# BUCKCONVERTER_-_POWER.net
KiCad netlist of a schematic drawn in Altium Designer
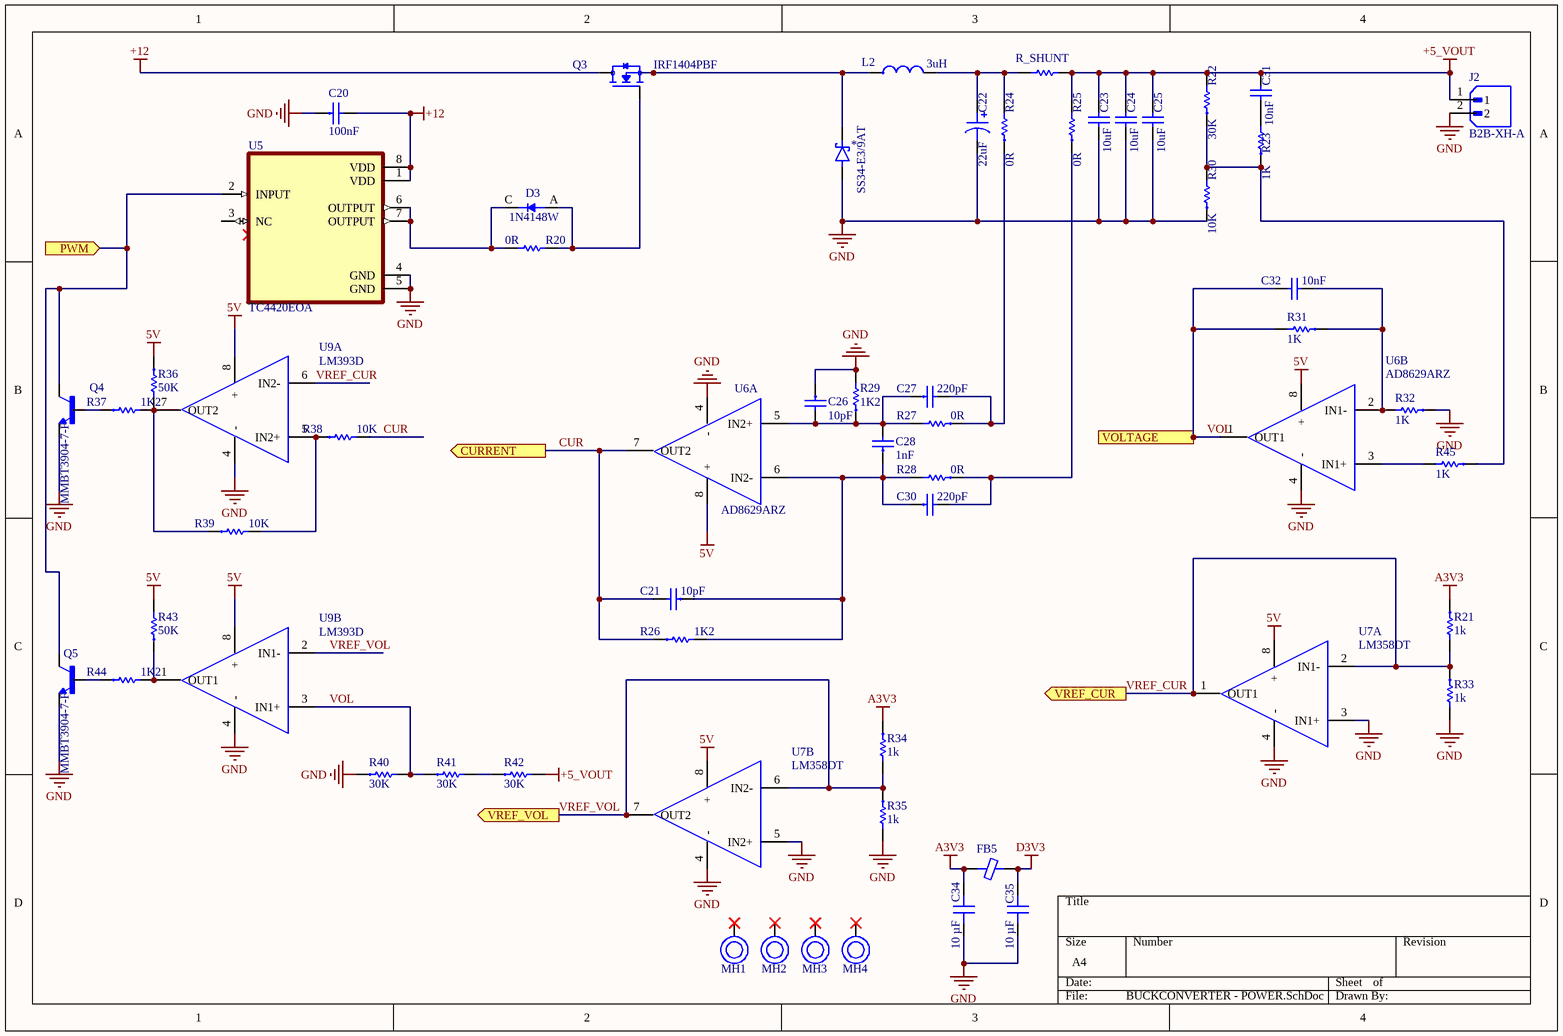
[diagram p0: BUCKCONVERTER - POWER.SchDoc]

(export (version "E")
  (design (tool "Eeschema 10.0.6"))
  (components
    (comp (ref "*")
      (value "SS34-E3/9AT")
      (footprint "SS34")
      (description "Rectifier Diode, Schottky, 1 Phase, 1 Element, 3A, 40V V(RRM), Silicon, DO-214AB")
      (fields (field (name "MANUFACTURER") "Vishay"))
      (libsource (lib "Schlib2") (part "SS34-E3/9AT"))
    )
    (comp (ref "C20")
      (value "100nF")
      (footprint "CAP-CER0402-20mil")
      (description "CAP CER 10uF 20% 6.3V X5R 0402 SMD")
      (libsource (lib "2502-GMQLITE-MAIN") (part "CAPCER0040 10uF 20% 6.3V X5R 0402 SMD"))
    )
    (comp (ref "C21")
      (value "10pF")
      (footprint "CAP-CER0603-0.8H")
      (description "CAP CER 220pF 10% 50V X7R 0603 SMD")
      (libsource (lib "2502-GMQLITE-MAIN") (part "CAPCER0003 220pF 10% 50V X7R 0603 SMD"))
    )
    (comp (ref "C22")
      (value "22uF")
      (footprint "330UF-5mm")
      (libsource (lib "Stm32_Flyback_Driver_250814_1") (part "CAP 47uF 63V_1"))
    )
    (comp (ref "C23")
      (value "10uF")
      (footprint "Cap cer 0603")
      (description "SMD Multilayer Ceramic Capacitor, 10 ï¿½F, 25 V, 0603 [1608 Metric], ï¿½ 20%, X5R")
      (fields
        (field (name "MANUFACTURER") "Murata")
        (field (name "MANUFACTURER PART NUMBER") "GRT188R61E106ME13D")
      )
      (libsource (lib "POWER_PIN_CAMERA") (part "GRT188R61E106ME13D"))
    )
    (comp (ref "C24")
      (value "10uF")
      (footprint "Cap cer 0603")
      (description "SMD Multilayer Ceramic Capacitor, 10 ï¿½F, 25 V, 0603 [1608 Metric], ï¿½ 20%, X5R")
      (fields
        (field (name "MANUFACTURER") "Murata")
        (field (name "MANUFACTURER PART NUMBER") "GRT188R61E106ME13D")
      )
      (libsource (lib "POWER_PIN_CAMERA") (part "GRT188R61E106ME13D"))
    )
    (comp (ref "C25")
      (value "10uF")
      (footprint "Cap cer 0603")
      (description "SMD Multilayer Ceramic Capacitor, 10 ï¿½F, 25 V, 0603 [1608 Metric], ï¿½ 20%, X5R")
      (fields
        (field (name "MANUFACTURER") "Murata")
        (field (name "MANUFACTURER PART NUMBER") "GRT188R61E106ME13D")
      )
      (libsource (lib "POWER_PIN_CAMERA") (part "GRT188R61E106ME13D"))
    )
    (comp (ref "C26")
      (value "10pF")
      (footprint "CAP-CER0603-0.8H")
      (description "CAP CER 220pF 10% 50V X7R 0603 SMD")
      (libsource (lib "2502-GMQLITE-MAIN") (part "CAPCER0003 220pF 10% 50V X7R 0603 SMD"))
    )
    (comp (ref "C27")
      (value "220pF")
      (footprint "CAP-CER0603-0.8H")
      (description "CAP CER 220pF 10% 50V X7R 0603 SMD")
      (libsource (lib "2502-GMQLITE-MAIN") (part "CAPCER0003 220pF 10% 50V X7R 0603 SMD"))
    )
    (comp (ref "C28")
      (value "1nF")
      (footprint "CAP-CER0603-0.8H")
      (description "CAP CER 220pF 10% 50V X7R 0603 SMD")
      (libsource (lib "2502-GMQLITE-MAIN") (part "CAPCER0003 220pF 10% 50V X7R 0603 SMD"))
    )
    (comp (ref "C30")
      (value "220pF")
      (footprint "CAP-CER0603-0.8H")
      (description "CAP CER 220pF 10% 50V X7R 0603 SMD")
      (libsource (lib "2502-GMQLITE-MAIN") (part "CAPCER0003 220pF 10% 50V X7R 0603 SMD"))
    )
    (comp (ref "C31")
      (value "10nF")
      (footprint "Cap cer 0603")
      (description "SMD Multilayer Ceramic Capacitor, 10 ï¿½F, 25 V, 0603 [1608 Metric], ï¿½ 20%, X5R")
      (fields
        (field (name "MANUFACTURER") "Murata")
        (field (name "MANUFACTURER PART NUMBER") "GRT188R61E106ME13D")
      )
      (libsource (lib "POWER_PIN_CAMERA") (part "GRT188R61E106ME13D"))
    )
    (comp (ref "C32")
      (value "10nF")
      (footprint "Cap cer 0603")
      (description "SMD Multilayer Ceramic Capacitor, 10 ï¿½F, 25 V, 0603 [1608 Metric], ï¿½ 20%, X5R")
      (fields
        (field (name "MANUFACTURER") "Murata")
        (field (name "MANUFACTURER PART NUMBER") "GRT188R61E106ME13D")
      )
      (libsource (lib "POWER_PIN_CAMERA") (part "GRT188R61E106ME13D"))
    )
    (comp (ref "C34")
      (value "10 µF")
      (footprint "CAP 0603")
      (description "CAP0603 X7R 10UF 10% 10V")
      (fields
        (field (name "PART NUMBER") "GMC10X7R106K10NT")
        (field (name "MANUFACTURER") "Cal-Chip Electronics, Inc.")
      )
      (libsource (lib "Celestial Altium Library - altium_library") (part "Capacitor"))
    )
    (comp (ref "C35")
      (value "10 µF")
      (footprint "CAP 0603")
      (description "CAP0603 X7R 10UF 10% 10V")
      (fields
        (field (name "PART NUMBER") "GMC10X7R106K10NT")
        (field (name "MANUFACTURER") "Cal-Chip Electronics, Inc.")
      )
      (libsource (lib "Celestial Altium Library - altium_library") (part "Capacitor"))
    )
    (comp (ref "D3")
      (value "1N4148W")
      (footprint "1N4148")
      (description "Small Signal Diode, Single, 100 V, 300 Ma, 1.25 V, 4 Ns, 2 A Rohs Compliant: Yes")
      (fields (field (name "MANUFACTURER") "Diodes") (field (name "MANUFACTURER PART NUMBER") "1N4148W-7-F"))
      (libsource (lib "POWER_PIN_CAMERA") (part "1N4148W-7-F"))
    )
    (comp (ref "FB5")
      (value "330 Ohms @ 100 MHz")
      (footprint "FB_0603")
      (description "FERRITE BEAD 330 OHM 0603 1LN")
      (fields
        (field (name "PART NUMBER") "BLM18KG331SH1D")
        (field (name "MANUFACTURER") "Murata Electronics")
      )
      (libsource (lib "Celestial Altium Library - altium_library") (part "Ferrite Chip"))
    )
    (comp (ref "J2")
      (value "B2B-XH-A")
      (footprint "JST_B2B-XH-A")
      (fields (field (name "MF") "{'manufacturer': u'JST Sales America Inc.'}"))
      (libsource (lib "B2B-XH-A") (part "B2B-XH-A"))
    )
    (comp (ref "L2")
      (value "3uH")
      (footprint "IND-06030-1uH")
      (description "IND MOI 1W2T 1.5uH 20% 14A 0630 SMD")
      (libsource (lib "2502-GMQLITE-MAIN") (part "INDMOI0013 1W2T 1.5uH 20% 14A 0630 SMD"))
    )
    (comp (ref "MH1") (value "MOUNTING HOLE") (footprint "M3") (libsource (lib "INVERTER") (part "MH")))
    (comp (ref "MH2") (value "MOUNTING HOLE") (footprint "M3") (libsource (lib "INVERTER") (part "MH")))
    (comp (ref "MH3") (value "MOUNTING HOLE") (footprint "M3") (libsource (lib "INVERTER") (part "MH")))
    (comp (ref "MH4") (value "MOUNTING HOLE") (footprint "M3") (libsource (lib "INVERTER") (part "MH")))
    (comp (ref "Q3")
      (value "IRF1404PBF")
      (footprint "TO220 AB")
      (description "Single N-Channel 40 V 0.004 Ohm 196 nC HEXFET® Power Mosfet - TO-220-3")
      (fields (field (name "MANUFACTURER") "Infineon"))
      (libsource (lib "Schlib2") (part "IRF1404PBF"))
    )
    (comp (ref "Q4")
      (value "MMBT3904-7-F")
      (footprint "MMBT3904")
      (description "Transistor General Purpose BJT NPN 40 Volt 0.2A Automotive 3-Pin SOT-23")
      (fields (field (name "MANUFACTURER") "Diodes Zetex"))
      (libsource (lib "POWER_PIN_CAMERA") (part "MMBT3904-7-F"))
    )
    (comp (ref "Q5")
      (value "MMBT3904-7-F")
      (footprint "MMBT3904")
      (description "Transistor General Purpose BJT NPN 40 Volt 0.2A Automotive 3-Pin SOT-23")
      (fields (field (name "MANUFACTURER") "Diodes Zetex"))
      (libsource (lib "POWER_PIN_CAMERA") (part "MMBT3904-7-F"))
    )
    (comp (ref "R20")
      (value "0R")
      (footprint "Res 0603")
      (description "Res Thick Film 0603 0 Ohm Pad SMD T/R")
      (fields
        (field (name "MANUFACTURER") "Vishay")
        (field (name "MANUFACTURER PART NUMBER") "CRCW06030000Z0EBC")
      )
      (libsource (lib "POWER_PIN_CAMERA") (part "Resistor 0R"))
    )
    (comp (ref "R21")
      (value "1k")
      (footprint "RES-CHP0402-0.35H")
      (description "RES CHP 33K 1% 1/16W 0402 SMD")
      (libsource (lib "2502-GMQLITE-MAIN") (part "RESCHP0085 33K 1% 0402 SMD"))
    )
    (comp (ref "R22")
      (value "30K")
      (footprint "RES-CHP0603-0.45H-272")
      (description "RES CHP 2K7 1% 1/10W 0603 SMD")
      (libsource (lib "2502-GMQLITE-MAIN") (part "RESCHP0195 2K7 1% 0603 SMD"))
    )
    (comp (ref "R23")
      (value "1K")
      (footprint "RES-CHP0603-0.45H-272")
      (description "RES CHP 2K7 1% 1/10W 0603 SMD")
      (libsource (lib "2502-GMQLITE-MAIN") (part "RESCHP0195 2K7 1% 0603 SMD"))
    )
    (comp (ref "R24")
      (value "0R")
      (footprint "RES-CHP0603-0.45H-272")
      (description "RES CHP 2K7 1% 1/10W 0603 SMD")
      (libsource (lib "2502-GMQLITE-MAIN") (part "RESCHP0195 2K7 1% 0603 SMD"))
    )
    (comp (ref "R25")
      (value "0R")
      (footprint "RES-CHP0603-0.45H-272")
      (description "RES CHP 2K7 1% 1/10W 0603 SMD")
      (libsource (lib "2502-GMQLITE-MAIN") (part "RESCHP0195 2K7 1% 0603 SMD"))
    )
    (comp (ref "R26")
      (value "1K2")
      (footprint "RES-CHP0603-0.45H-272")
      (description "RES CHP 2K7 1% 1/10W 0603 SMD")
      (libsource (lib "2502-GMQLITE-MAIN") (part "RESCHP0195 2K7 1% 0603 SMD"))
    )
    (comp (ref "R27")
      (value "0R")
      (footprint "RES-CHP0603-0.45H-272")
      (description "RES CHP 2K7 1% 1/10W 0603 SMD")
      (libsource (lib "2502-GMQLITE-MAIN") (part "RESCHP0195 2K7 1% 0603 SMD"))
    )
    (comp (ref "R28")
      (value "0R")
      (footprint "RES-CHP0603-0.45H-272")
      (description "RES CHP 2K7 1% 1/10W 0603 SMD")
      (libsource (lib "2502-GMQLITE-MAIN") (part "RESCHP0195 2K7 1% 0603 SMD"))
    )
    (comp (ref "R29")
      (value "1K2")
      (footprint "RES-CHP0603-0.45H-272")
      (description "RES CHP 2K7 1% 1/10W 0603 SMD")
      (libsource (lib "2502-GMQLITE-MAIN") (part "RESCHP0195 2K7 1% 0603 SMD"))
    )
    (comp (ref "R30")
      (value "10K")
      (footprint "RES-CHP0603-0.45H-272")
      (description "RES CHP 2K7 1% 1/10W 0603 SMD")
      (libsource (lib "2502-GMQLITE-MAIN") (part "RESCHP0195 2K7 1% 0603 SMD"))
    )
    (comp (ref "R31")
      (value "1K")
      (footprint "RES-CHP0603-0.45H-272")
      (description "RES CHP 2K7 1% 1/10W 0603 SMD")
      (libsource (lib "2502-GMQLITE-MAIN") (part "RESCHP0195 2K7 1% 0603 SMD"))
    )
    (comp (ref "R32")
      (value "1K")
      (footprint "RES-CHP0603-0.45H-272")
      (description "RES CHP 2K7 1% 1/10W 0603 SMD")
      (libsource (lib "2502-GMQLITE-MAIN") (part "RESCHP0195 2K7 1% 0603 SMD"))
    )
    (comp (ref "R33")
      (value "1k")
      (footprint "RES-CHP0402-0.35H")
      (description "RES CHP 33K 1% 1/16W 0402 SMD")
      (libsource (lib "2502-GMQLITE-MAIN") (part "RESCHP0085 33K 1% 0402 SMD"))
    )
    (comp (ref "R34")
      (value "1k")
      (footprint "RES-CHP0402-0.35H")
      (description "RES CHP 33K 1% 1/16W 0402 SMD")
      (libsource (lib "2502-GMQLITE-MAIN") (part "RESCHP0085 33K 1% 0402 SMD"))
    )
    (comp (ref "R35")
      (value "1k")
      (footprint "RES-CHP0402-0.35H")
      (description "RES CHP 33K 1% 1/16W 0402 SMD")
      (libsource (lib "2502-GMQLITE-MAIN") (part "RESCHP0085 33K 1% 0402 SMD"))
    )
    (comp (ref "R36")
      (value "50K")
      (footprint "RES-CHP0603-0.45H-272")
      (description "RES CHP 2K7 1% 1/10W 0603 SMD")
      (libsource (lib "2502-GMQLITE-MAIN") (part "RESCHP0195 2K7 1% 0603 SMD"))
    )
    (comp (ref "R37")
      (value "1K2")
      (footprint "RES-CHP0603-0.45H-272")
      (description "RES CHP 2K7 1% 1/10W 0603 SMD")
      (libsource (lib "2502-GMQLITE-MAIN") (part "RESCHP0195 2K7 1% 0603 SMD"))
    )
    (comp (ref "R38")
      (value "10K")
      (footprint "RES-CHP0603-0.45H-272")
      (description "RES CHP 2K7 1% 1/10W 0603 SMD")
      (libsource (lib "2502-GMQLITE-MAIN") (part "RESCHP0195 2K7 1% 0603 SMD"))
    )
    (comp (ref "R39")
      (value "10K")
      (footprint "RES-CHP0603-0.45H-272")
      (description "RES CHP 2K7 1% 1/10W 0603 SMD")
      (libsource (lib "2502-GMQLITE-MAIN") (part "RESCHP0195 2K7 1% 0603 SMD"))
    )
    (comp (ref "R40")
      (value "30K")
      (footprint "RES-CHP0402-0.35H")
      (description "RES CHP 33K 1% 1/16W 0402 SMD")
      (libsource (lib "2502-GMQLITE-MAIN") (part "RESCHP0085 33K 1% 0402 SMD"))
    )
    (comp (ref "R41")
      (value "30K")
      (footprint "RES-CHP0402-0.35H")
      (description "RES CHP 33K 1% 1/16W 0402 SMD")
      (libsource (lib "2502-GMQLITE-MAIN") (part "RESCHP0085 33K 1% 0402 SMD"))
    )
    (comp (ref "R42")
      (value "30K")
      (footprint "RES-CHP0402-0.35H")
      (description "RES CHP 33K 1% 1/16W 0402 SMD")
      (libsource (lib "2502-GMQLITE-MAIN") (part "RESCHP0085 33K 1% 0402 SMD"))
    )
    (comp (ref "R43")
      (value "50K")
      (footprint "RES-CHP0603-0.45H-272")
      (description "RES CHP 2K7 1% 1/10W 0603 SMD")
      (libsource (lib "2502-GMQLITE-MAIN") (part "RESCHP0195 2K7 1% 0603 SMD"))
    )
    (comp (ref "R44")
      (value "1K2")
      (footprint "RES-CHP0603-0.45H-272")
      (description "RES CHP 2K7 1% 1/10W 0603 SMD")
      (libsource (lib "2502-GMQLITE-MAIN") (part "RESCHP0195 2K7 1% 0603 SMD"))
    )
    (comp (ref "R45")
      (value "1K")
      (footprint "RES-CHP0603-0.45H-272")
      (description "RES CHP 2K7 1% 1/10W 0603 SMD")
      (libsource (lib "2502-GMQLITE-MAIN") (part "RESCHP0195 2K7 1% 0603 SMD"))
    )
    (comp (ref "R_SHUNT")
      (value "0.01R")
      (footprint "R_SHUNT")
      (libsource (lib "Stm32_Flyback_Driver_250814_1") (part "R_SHUNT"))
    )
    (comp (ref "U5")
      (value "TC4420EOA")
      (footprint "SOIC127P600X175-8N")
      (fields (field (name "MF") "Microchip"))
      (libsource (lib "TC4420EOA") (part "TC4420EOA"))
    )
    (comp (ref "U6")
      (value "AD8629ARZ")
      (footprint "AD8629ARZ")
      (description "IC OPAMP ZERO-DRIFT 2 CIRC 8SOIC Zero-Drift Amplifier 2 Circuit Rail-to-Rail 8-SOIC")
      (fields (field (name "MANUFACTURER") "Analog Devices"))
      (libsource (lib "Schlib2") (part "AD8629ARZ"))
    )
    (comp (ref "U7")
      (value "LM358DT")
      (footprint "SOIC 8")
      (description "Operational Amplifier, 2-Channels, 1.1 MHz, 0.6 V/us, 3 V to 30 V, 8 Pins, SOIC")
      (fields (field (name "MANUFACTURER") "STMicroelectronics"))
      (libsource (lib "Stm32_Flyback_Driver_250814_1") (part "LM358DT"))
    )
    (comp (ref "U9")
      (value "LM393D")
      (footprint "LM393")
      (description "LM393 Series Dual 36 V 250 nA SMT Low Power Voltage Comparator - SOIC-8")
      (fields (field (name "MANUFACTURER") "STMicroelectronics"))
      (libsource (lib "BUCKCONVERTER") (part "LM393D"))
    )
  )
  (nets
    (net (code "1") (name "+5_VOUT") (class "Default")
      (node (ref "C23") (pin "2") (pinfunction "2_2") (pintype "passive"))
      (node (ref "C24") (pin "2") (pinfunction "2_2") (pintype "passive"))
      (node (ref "C25") (pin "2") (pinfunction "2_2") (pintype "passive"))
      (node (ref "C31") (pin "2") (pinfunction "2_2") (pintype "passive"))
      (node (ref "J2") (pin "1") (pinfunction "1_1") (pintype "passive"))
      (node (ref "R22") (pin "2") (pinfunction "2_2") (pintype "passive"))
      (node (ref "R25") (pin "2") (pinfunction "2_2") (pintype "passive"))
      (node (ref "R42") (pin "2") (pinfunction "2_2") (pintype "passive"))
      (node (ref "R_SHUNT") (pin "2") (pinfunction "2_2") (pintype "passive"))
    )
    (net (code "2") (name "+12") (class "Default")
      (node (ref "C20") (pin "2") (pinfunction "2_2") (pintype "passive"))
      (node (ref "Q3") (pin "2") (pinfunction "D_2") (pintype "passive"))
      (node (ref "U5") (pin "1") (pinfunction "VDD_1") (pintype "power_in"))
      (node (ref "U5") (pin "8") (pinfunction "VDD_8") (pintype "power_in"))
    )
    (net (code "3") (name "/CUR") (class "Default")
      (node (ref "C21") (pin "2") (pinfunction "2_2") (pintype "passive"))
      (node (ref "R26") (pin "1") (pinfunction "1_1") (pintype "passive"))
      (node (ref "R38") (pin "2") (pinfunction "2_2") (pintype "passive"))
      (node (ref "U6") (pin "7") (pinfunction "OUT2_7") (pintype "passive"))
    )
    (net (code "4") (name "/PWM") (class "Default")
      (node (ref "Q4") (pin "C") (pinfunction "C_C") (pintype "passive"))
      (node (ref "Q5") (pin "C") (pinfunction "C_C") (pintype "passive"))
      (node (ref "U5") (pin "2") (pinfunction "INPUT_2") (pintype "input"))
    )
    (net (code "5") (name "/VOL") (class "Default")
      (node (ref "C32") (pin "2") (pinfunction "2_2") (pintype "passive"))
      (node (ref "R31") (pin "2") (pinfunction "2_2") (pintype "passive"))
      (node (ref "R40") (pin "2") (pinfunction "2_2") (pintype "passive"))
      (node (ref "R41") (pin "1") (pinfunction "1_1") (pintype "passive"))
      (node (ref "U6") (pin "1") (pinfunction "OUT1_1") (pintype "passive"))
      (node (ref "U9") (pin "3") (pinfunction "IN1+_3") (pintype "passive"))
    )
    (net (code "6") (name "/VREF_CUR") (class "Default")
      (node (ref "R21") (pin "2") (pinfunction "2_2") (pintype "passive"))
      (node (ref "R33") (pin "1") (pinfunction "1_1") (pintype "passive"))
      (node (ref "U7") (pin "1") (pinfunction "OUT1_1") (pintype "passive"))
      (node (ref "U7") (pin "2") (pinfunction "IN1-_2") (pintype "passive"))
      (node (ref "U9") (pin "6") (pinfunction "IN2-_6") (pintype "passive"))
    )
    (net (code "7") (name "/VREF_VOL") (class "Default")
      (node (ref "R34") (pin "2") (pinfunction "2_2") (pintype "passive"))
      (node (ref "R35") (pin "1") (pinfunction "1_1") (pintype "passive"))
      (node (ref "U7") (pin "6") (pinfunction "IN2-_6") (pintype "passive"))
      (node (ref "U7") (pin "7") (pinfunction "OUT2_7") (pintype "passive"))
      (node (ref "U9") (pin "2") (pinfunction "IN1-_2") (pintype "passive"))
    )
    (net (code "8") (name "5V") (class "Default")
      (node (ref "R36") (pin "1") (pinfunction "1_1") (pintype "passive"))
      (node (ref "R43") (pin "2") (pinfunction "2_2") (pintype "passive"))
      (node (ref "U6") (pin "8") (pinfunction "+_8") (pintype "passive"))
      (node (ref "U7") (pin "8") (pinfunction "+_8") (pintype "passive"))
      (node (ref "U9") (pin "8") (pinfunction "+_8") (pintype "passive"))
    )
    (net (code "9") (name "A3V3") (class "Default")
      (node (ref "C34") (pin "2") (pinfunction "2_2") (pintype "passive"))
      (node (ref "FB5") (pin "1") (pinfunction "1_1") (pintype "passive"))
      (node (ref "R21") (pin "1") (pinfunction "1_1") (pintype "passive"))
      (node (ref "R34") (pin "1") (pinfunction "1_1") (pintype "passive"))
    )
    (net (code "10") (name "D3V3") (class "Default")
      (node (ref "C35") (pin "2") (pinfunction "2_2") (pintype "passive"))
      (node (ref "FB5") (pin "2") (pinfunction "2_2") (pintype "passive"))
    )
    (net (code "11") (name "GND") (class "Default")
      (node (ref "*") (pin "A") (pinfunction "A_A") (pintype "passive"))
      (node (ref "C20") (pin "1") (pinfunction "1_1") (pintype "passive"))
      (node (ref "C22") (pin "2") (pinfunction "2_2") (pintype "passive"))
      (node (ref "C23") (pin "1") (pinfunction "1_1") (pintype "passive"))
      (node (ref "C24") (pin "1") (pinfunction "1_1") (pintype "passive"))
      (node (ref "C25") (pin "1") (pinfunction "1_1") (pintype "passive"))
      (node (ref "C26") (pin "1") (pinfunction "1_1") (pintype "passive"))
      (node (ref "C34") (pin "1") (pinfunction "1_1") (pintype "passive"))
      (node (ref "C35") (pin "1") (pinfunction "1_1") (pintype "passive"))
      (node (ref "J2") (pin "2") (pinfunction "2_2") (pintype "passive"))
      (node (ref "Q4") (pin "E") (pinfunction "E_E") (pintype "passive"))
      (node (ref "Q5") (pin "E") (pinfunction "E_E") (pintype "passive"))
      (node (ref "R29") (pin "2") (pinfunction "2_2") (pintype "passive"))
      (node (ref "R30") (pin "1") (pinfunction "1_1") (pintype "passive"))
      (node (ref "R32") (pin "1") (pinfunction "1_1") (pintype "passive"))
      (node (ref "R33") (pin "2") (pinfunction "2_2") (pintype "passive"))
      (node (ref "R35") (pin "2") (pinfunction "2_2") (pintype "passive"))
      (node (ref "R40") (pin "1") (pinfunction "1_1") (pintype "passive"))
      (node (ref "U5") (pin "4") (pinfunction "GND_4") (pintype "power_in"))
      (node (ref "U5") (pin "5") (pinfunction "GND_5") (pintype "power_in"))
      (node (ref "U6") (pin "4") (pinfunction "-_4") (pintype "passive"))
      (node (ref "U7") (pin "3") (pinfunction "IN1+_3") (pintype "passive"))
      (node (ref "U7") (pin "4") (pinfunction "-_4") (pintype "passive"))
      (node (ref "U7") (pin "5") (pinfunction "IN2+_5") (pintype "passive"))
      (node (ref "U9") (pin "4") (pinfunction "-_4") (pintype "passive"))
    )
    (net (code "12") (name "Net-(*-K)") (class "Default")
      (node (ref "*") (pin "C") (pinfunction "K_C") (pintype "passive"))
      (node (ref "L2") (pin "1") (pinfunction "1_1") (pintype "passive"))
      (node (ref "Q3") (pin "3") (pinfunction "S_3") (pintype "passive"))
    )
    (net (code "13") (name "Net-(C22-Pad1)") (class "Default")
      (node (ref "C22") (pin "1") (pinfunction "1_1") (pintype "passive"))
      (node (ref "L2") (pin "2") (pinfunction "2_2") (pintype "passive"))
      (node (ref "R24") (pin "2") (pinfunction "2_2") (pintype "passive"))
      (node (ref "R_SHUNT") (pin "1") (pinfunction "1_1") (pintype "passive"))
    )
    (net (code "14") (name "Net-(C27-Pad2)") (class "Default")
      (node (ref "C27") (pin "2") (pinfunction "2_2") (pintype "passive"))
      (node (ref "R24") (pin "1") (pinfunction "1_1") (pintype "passive"))
      (node (ref "R27") (pin "1") (pinfunction "1_1") (pintype "passive"))
    )
    (net (code "15") (name "Net-(C30-Pad2)") (class "Default")
      (node (ref "C30") (pin "2") (pinfunction "2_2") (pintype "passive"))
      (node (ref "R25") (pin "1") (pinfunction "1_1") (pintype "passive"))
      (node (ref "R28") (pin "1") (pinfunction "1_1") (pintype "passive"))
    )
    (net (code "16") (name "Net-(C31-Pad1)") (class "Default")
      (node (ref "C31") (pin "1") (pinfunction "1_1") (pintype "passive"))
      (node (ref "R23") (pin "2") (pinfunction "2_2") (pintype "passive"))
    )
    (net (code "17") (name "Net-(D3-K)") (class "Default")
      (node (ref "D3") (pin "C") (pinfunction "K_C") (pintype "passive"))
      (node (ref "R20") (pin "1") (pinfunction "1_1") (pintype "passive"))
      (node (ref "U5") (pin "6") (pinfunction "OUTPUT_6") (pintype "output"))
      (node (ref "U5") (pin "7") (pinfunction "OUTPUT_7") (pintype "output"))
    )
    (net (code "18") (name "Net-(Q3-G)") (class "Default")
      (node (ref "D3") (pin "A") (pinfunction "A_A") (pintype "passive"))
      (node (ref "Q3") (pin "1") (pinfunction "G_1") (pintype "passive"))
      (node (ref "R20") (pin "2") (pinfunction "2_2") (pintype "passive"))
    )
    (net (code "19") (name "Net-(Q4-PadB)") (class "Default")
      (node (ref "Q4") (pin "B") (pinfunction "B_B") (pintype "passive"))
      (node (ref "R37") (pin "1") (pinfunction "1_1") (pintype "passive"))
    )
    (net (code "20") (name "Net-(Q5-PadB)") (class "Default")
      (node (ref "Q5") (pin "B") (pinfunction "B_B") (pintype "passive"))
      (node (ref "R44") (pin "1") (pinfunction "1_1") (pintype "passive"))
    )
    (net (code "21") (name "Net-(R22-Pad1)") (class "Default")
      (node (ref "R22") (pin "1") (pinfunction "1_1") (pintype "passive"))
      (node (ref "R23") (pin "1") (pinfunction "1_1") (pintype "passive"))
      (node (ref "R30") (pin "2") (pinfunction "2_2") (pintype "passive"))
      (node (ref "R45") (pin "1") (pinfunction "1_1") (pintype "passive"))
    )
    (net (code "22") (name "Net-(R41-Pad2)") (class "Default")
      (node (ref "R41") (pin "2") (pinfunction "2_2") (pintype "passive"))
      (node (ref "R42") (pin "1") (pinfunction "1_1") (pintype "passive"))
    )
    (net (code "23") (name "Net-(U6A-IN2+)") (class "Default")
      (node (ref "C26") (pin "2") (pinfunction "2_2") (pintype "passive"))
      (node (ref "C27") (pin "1") (pinfunction "1_1") (pintype "passive"))
      (node (ref "C28") (pin "2") (pinfunction "2_2") (pintype "passive"))
      (node (ref "R27") (pin "2") (pinfunction "2_2") (pintype "passive"))
      (node (ref "R29") (pin "1") (pinfunction "1_1") (pintype "passive"))
      (node (ref "U6") (pin "5") (pinfunction "IN2+_5") (pintype "passive"))
    )
    (net (code "24") (name "Net-(U6A-IN2-)") (class "Default")
      (node (ref "C21") (pin "1") (pinfunction "1_1") (pintype "passive"))
      (node (ref "C28") (pin "1") (pinfunction "1_1") (pintype "passive"))
      (node (ref "C30") (pin "1") (pinfunction "1_1") (pintype "passive"))
      (node (ref "R26") (pin "2") (pinfunction "2_2") (pintype "passive"))
      (node (ref "R28") (pin "2") (pinfunction "2_2") (pintype "passive"))
      (node (ref "U6") (pin "6") (pinfunction "IN2-_6") (pintype "passive"))
    )
    (net (code "25") (name "Net-(U6B-IN1+)") (class "Default")
      (node (ref "R45") (pin "2") (pinfunction "2_2") (pintype "passive"))
      (node (ref "U6") (pin "3") (pinfunction "IN1+_3") (pintype "passive"))
    )
    (net (code "26") (name "Net-(U6B-IN1-)") (class "Default")
      (node (ref "C32") (pin "1") (pinfunction "1_1") (pintype "passive"))
      (node (ref "R31") (pin "1") (pinfunction "1_1") (pintype "passive"))
      (node (ref "R32") (pin "2") (pinfunction "2_2") (pintype "passive"))
      (node (ref "U6") (pin "2") (pinfunction "IN1-_2") (pintype "passive"))
    )
    (net (code "27") (name "Net-(U9A-IN2+)") (class "Default")
      (node (ref "R38") (pin "1") (pinfunction "1_1") (pintype "passive"))
      (node (ref "R39") (pin "2") (pinfunction "2_2") (pintype "passive"))
      (node (ref "U9") (pin "5") (pinfunction "IN2+_5") (pintype "passive"))
    )
    (net (code "28") (name "Net-(U9A-OUT2)") (class "Default")
      (node (ref "R36") (pin "2") (pinfunction "2_2") (pintype "passive"))
      (node (ref "R37") (pin "2") (pinfunction "2_2") (pintype "passive"))
      (node (ref "R39") (pin "1") (pinfunction "1_1") (pintype "passive"))
      (node (ref "U9") (pin "7") (pinfunction "OUT2_7") (pintype "passive"))
    )
    (net (code "29") (name "Net-(U9B-OUT1)") (class "Default")
      (node (ref "R43") (pin "1") (pinfunction "1_1") (pintype "passive"))
      (node (ref "R44") (pin "2") (pinfunction "2_2") (pintype "passive"))
      (node (ref "U9") (pin "1") (pinfunction "OUT1_1") (pintype "passive"))
    )
    (net (code "30") (name "unconnected-(MH1-GND-Pad1)") (class "Default")
      (node (ref "MH1") (pin "1") (pinfunction "GND_1") (pintype "passive+no_connect"))
    )
    (net (code "31") (name "unconnected-(MH2-GND-Pad1)") (class "Default")
      (node (ref "MH2") (pin "1") (pinfunction "GND_1") (pintype "passive+no_connect"))
    )
    (net (code "32") (name "unconnected-(MH3-GND-Pad1)") (class "Default")
      (node (ref "MH3") (pin "1") (pinfunction "GND_1") (pintype "passive+no_connect"))
    )
    (net (code "33") (name "unconnected-(MH4-GND-Pad1)") (class "Default")
      (node (ref "MH4") (pin "1") (pinfunction "GND_1") (pintype "passive+no_connect"))
    )
    (net (code "34") (name "unconnected-(U5-NC-Pad3)") (class "Default")
      (node (ref "U5") (pin "3") (pinfunction "NC_3") (pintype "bidirectional"))
    )
  )
)
